# 2040.net
KiCad netlist of a schematic drawn in Altium Designer
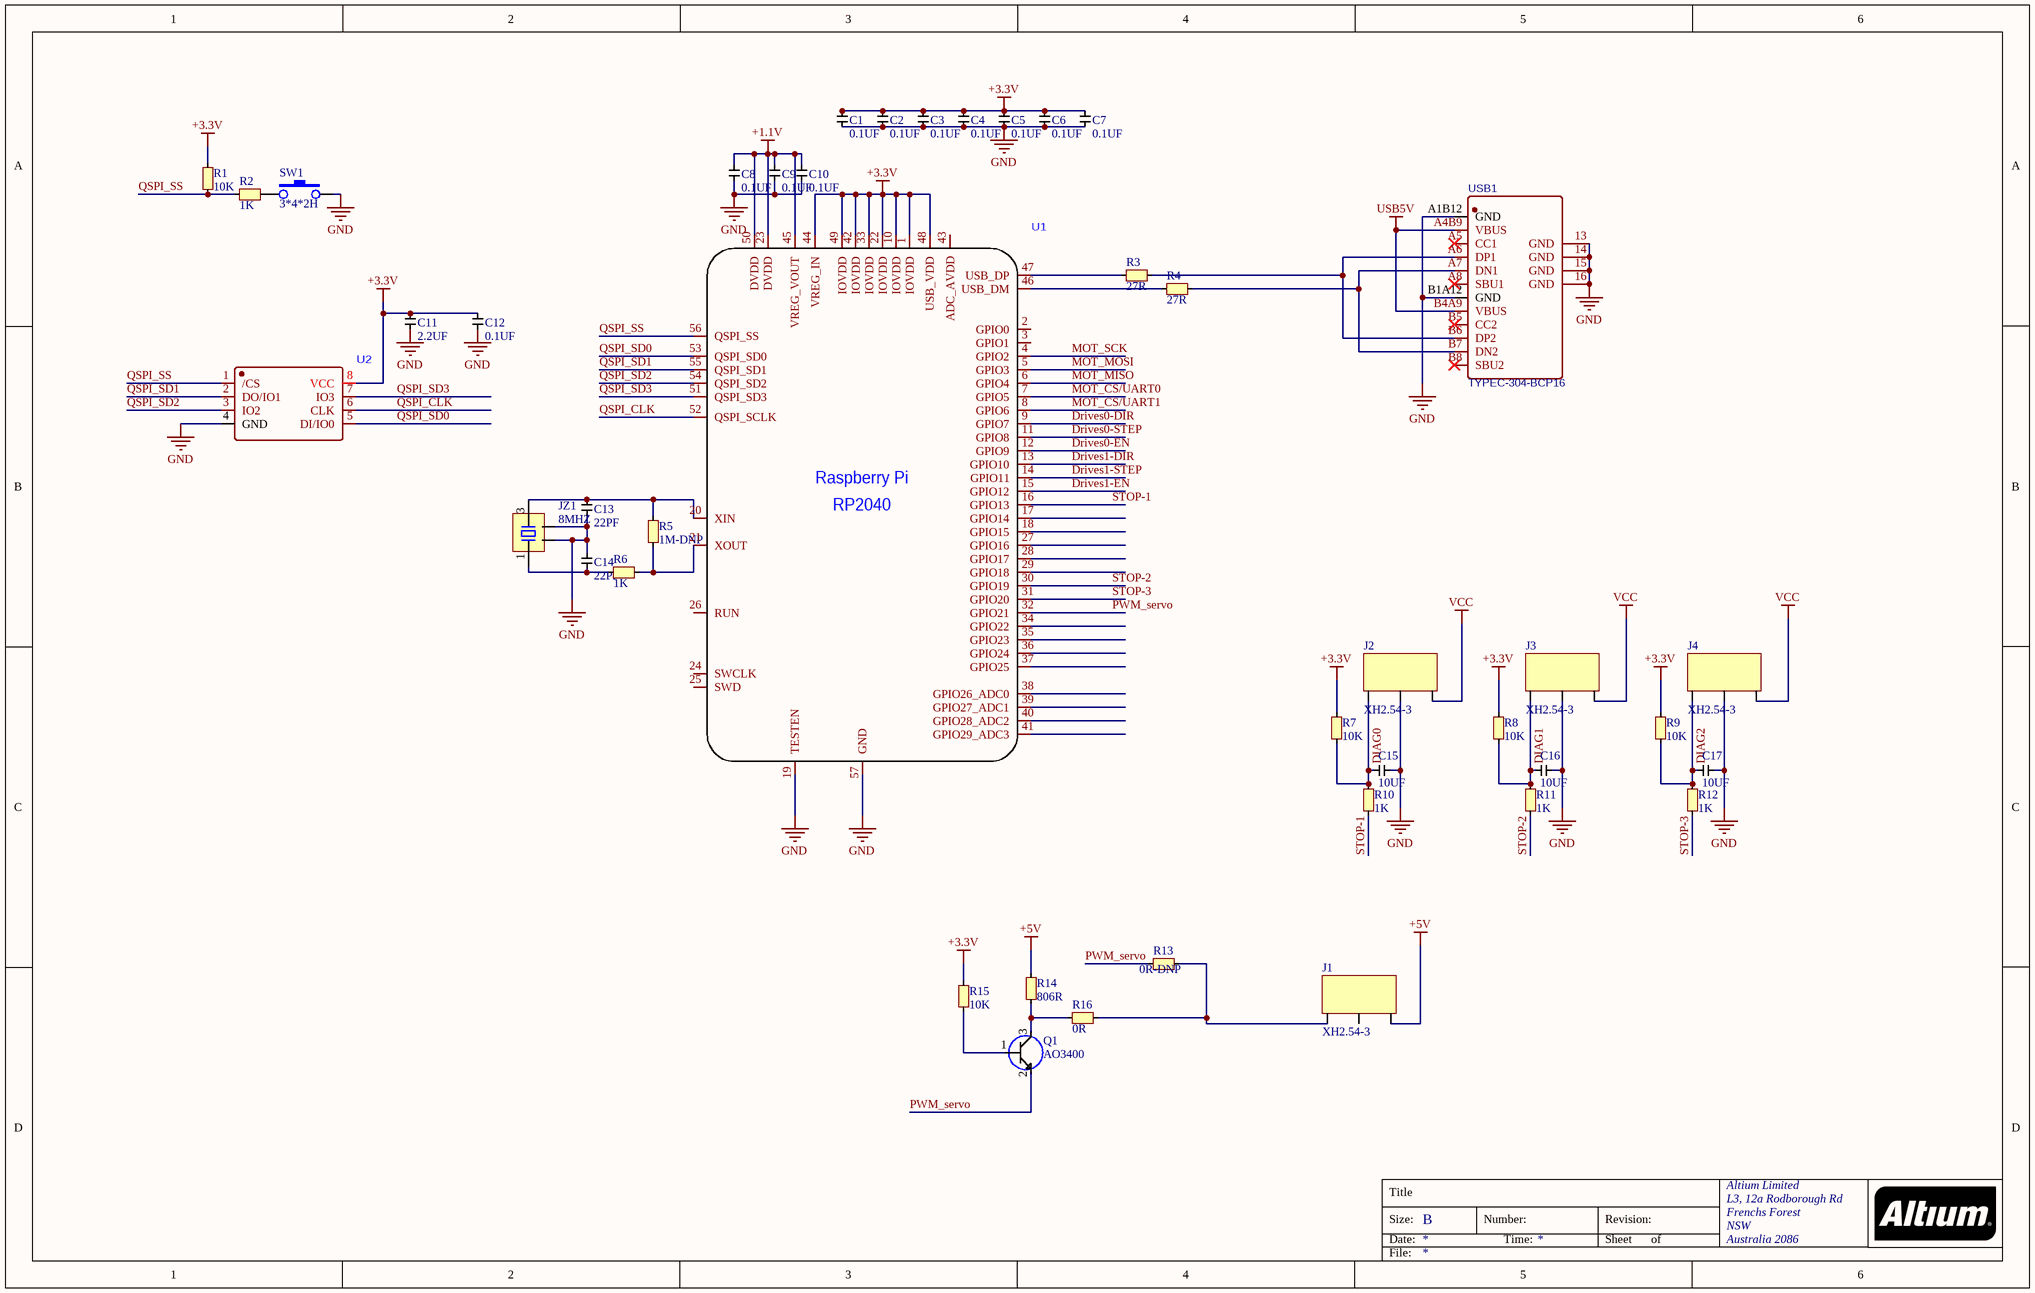
[diagram p0: 2040.SchDoc]

(export (version "E")
  (design (tool "Eeschema 10.0.6"))
  (components
    (comp (ref "C1") (value "0.1UF") (footprint "C0402") (libsource (lib "jx") (part "C")))
    (comp (ref "C2") (value "0.1UF") (footprint "C0402") (libsource (lib "jx") (part "C")))
    (comp (ref "C3") (value "0.1UF") (footprint "C0402") (libsource (lib "jx") (part "C")))
    (comp (ref "C4") (value "0.1UF") (footprint "C0402") (libsource (lib "jx") (part "C")))
    (comp (ref "C5") (value "0.1UF") (footprint "C0402") (libsource (lib "jx") (part "C")))
    (comp (ref "C6") (value "0.1UF") (footprint "C0402") (libsource (lib "jx") (part "C")))
    (comp (ref "C7") (value "0.1UF") (footprint "C0402") (libsource (lib "jx") (part "C")))
    (comp (ref "C8") (value "0.1UF") (footprint "C0402") (libsource (lib "jx") (part "C")))
    (comp (ref "C9") (value "0.1UF") (footprint "C0402") (libsource (lib "jx") (part "C")))
    (comp (ref "C10") (value "0.1UF") (footprint "C0402") (libsource (lib "jx") (part "C")))
    (comp (ref "C11") (value "2.2UF") (footprint "C0402") (libsource (lib "jx") (part "C")))
    (comp (ref "C12") (value "0.1UF") (footprint "C0402") (libsource (lib "jx") (part "C")))
    (comp (ref "C13") (value "22PF") (footprint "0603C") (libsource (lib "jx") (part "0603C")))
    (comp (ref "C14") (value "22PF") (footprint "0603C") (libsource (lib "jx") (part "0603C")))
    (comp (ref "C15") (value "10UF") (footprint "0603C") (libsource (lib "jx") (part "0603C")))
    (comp (ref "C16") (value "10UF") (footprint "0603C") (libsource (lib "jx") (part "0603C")))
    (comp (ref "C17") (value "10UF") (footprint "0603C") (libsource (lib "jx") (part "0603C")))
    (comp (ref "J1")
      (value "XH2.54-3")
      (footprint "JST_XH_B3B-XH-A_1X03_P2.50MM_VERTICAL")
      (libsource (lib "jx") (part "XH2.54-3"))
    )
    (comp (ref "J2")
      (value "XH2.54-3")
      (footprint "JST_XH_B3B-XH-A_1X03_P2.50MM_VERTICAL")
      (libsource (lib "jx") (part "XH2.54-3"))
    )
    (comp (ref "J3")
      (value "XH2.54-3")
      (footprint "JST_XH_B3B-XH-A_1X03_P2.50MM_VERTICAL")
      (libsource (lib "jx") (part "XH2.54-3"))
    )
    (comp (ref "J4")
      (value "XH2.54-3")
      (footprint "JST_XH_B3B-XH-A_1X03_P2.50MM_VERTICAL")
      (libsource (lib "jx") (part "XH2.54-3"))
    )
    (comp (ref "JZ1") (value "8MHZ") (footprint "OSC-3225-4P") (libsource (lib "jx") (part "JZ3225")))
    (comp (ref "Q1") (value "AO3400") (footprint "SOT-23") (libsource (lib "jx") (part "S8050")))
    (comp (ref "R1") (value "10K") (footprint "0603") (libsource (lib "") (part "0603R_3")))
    (comp (ref "R2") (value "1K") (footprint "0603") (libsource (lib "jx") (part "0603R")))
    (comp (ref "R3") (value "27R") (footprint "R0402") (libsource (lib "") (part "R_1")))
    (comp (ref "R4") (value "27R") (footprint "R0402") (libsource (lib "") (part "R_1")))
    (comp (ref "R5") (value "1M-DNP") (footprint "0603") (libsource (lib "") (part "0603R_1")))
    (comp (ref "R6") (value "1K") (footprint "0603") (libsource (lib "") (part "0603R_2")))
    (comp (ref "R7") (value "10K") (footprint "0603") (libsource (lib "") (part "0603R_1")))
    (comp (ref "R8") (value "10K") (footprint "0603") (libsource (lib "") (part "0603R_1")))
    (comp (ref "R9") (value "10K") (footprint "0603") (libsource (lib "") (part "0603R_1")))
    (comp (ref "R10") (value "1K") (footprint "0603") (libsource (lib "") (part "0603R_1")))
    (comp (ref "R11") (value "1K") (footprint "0603") (libsource (lib "") (part "0603R_1")))
    (comp (ref "R12") (value "1K") (footprint "0603") (libsource (lib "") (part "0603R_1")))
    (comp (ref "R13") (value "0R-DNP") (footprint "0603") (libsource (lib "") (part "R_2")))
    (comp (ref "R14") (value "806R") (footprint "0603") (libsource (lib "") (part "R_3")))
    (comp (ref "R15") (value "10K") (footprint "0603") (libsource (lib "jx") (part "R")))
    (comp (ref "R16") (value "0R") (footprint "0603") (libsource (lib "") (part "R_2")))
    (comp (ref "SW1") (value "3*4*2H") (footprint "K") (libsource (lib "jx") (part "RESET")))
    (comp (ref "U1")
      (value "~")
      (footprint "RP2040")
      (libsource (lib "altium-import") (part "root_0_RP2040_"))
    )
    (comp (ref "U2")
      (value "~")
      (footprint "SOP-8")
      (libsource (lib "altium-import") (part "root_0_W25Q16JVSSIQ_"))
    )
    (comp (ref "USB1")
      (value "TYPEC-304-BCP16")
      (footprint "USB-C-SMD_TYPEC-304-BCP16")
      (fields (field (name "BOM_SUPPLIER PART") "C720629") (field (name "CONTRIBUTOR") "LCSC"))
      (libsource (lib "altium-import") (part "root_0_TYPEC-304-BCP16_"))
    )
  )
  (nets
    (net (code "1") (name "+1.1V") (class "Default")
      (node (ref "C10") (pin "1") (pinfunction "1_1") (pintype "passive"))
      (node (ref "C8") (pin "1") (pinfunction "1_1") (pintype "passive"))
      (node (ref "C9") (pin "1") (pinfunction "1_1") (pintype "passive"))
      (node (ref "U1") (pin "23") (pinfunction "DVDD_23") (pintype "passive"))
      (node (ref "U1") (pin "45") (pinfunction "VREG_VOUT_45") (pintype "passive"))
      (node (ref "U1") (pin "50") (pinfunction "DVDD_50") (pintype "passive"))
    )
    (net (code "2") (name "+3.3V") (class "Default")
      (node (ref "C1") (pin "1") (pinfunction "1_1") (pintype "passive"))
      (node (ref "C11") (pin "1") (pinfunction "1_1") (pintype "passive"))
      (node (ref "C12") (pin "1") (pinfunction "1_1") (pintype "passive"))
      (node (ref "C2") (pin "1") (pinfunction "1_1") (pintype "passive"))
      (node (ref "C3") (pin "1") (pinfunction "1_1") (pintype "passive"))
      (node (ref "C4") (pin "1") (pinfunction "1_1") (pintype "passive"))
      (node (ref "C5") (pin "1") (pinfunction "1_1") (pintype "passive"))
      (node (ref "C6") (pin "1") (pinfunction "1_1") (pintype "passive"))
      (node (ref "C7") (pin "1") (pinfunction "1_1") (pintype "passive"))
      (node (ref "R1") (pin "1") (pinfunction "1_1") (pintype "passive"))
      (node (ref "R15") (pin "1") (pinfunction "1_1") (pintype "passive"))
      (node (ref "R7") (pin "2") (pinfunction "2_2") (pintype "passive"))
      (node (ref "R8") (pin "2") (pinfunction "2_2") (pintype "passive"))
      (node (ref "R9") (pin "2") (pinfunction "2_2") (pintype "passive"))
      (node (ref "U1") (pin "1") (pinfunction "IOVDD_1") (pintype "passive"))
      (node (ref "U1") (pin "10") (pinfunction "IOVDD_10") (pintype "passive"))
      (node (ref "U1") (pin "22") (pinfunction "IOVDD_22") (pintype "passive"))
      (node (ref "U1") (pin "33") (pinfunction "IOVDD_33") (pintype "passive"))
      (node (ref "U1") (pin "42") (pinfunction "IOVDD_42") (pintype "passive"))
      (node (ref "U1") (pin "44") (pinfunction "VREG_IN_44") (pintype "passive"))
      (node (ref "U1") (pin "48") (pinfunction "USB_VDD_48") (pintype "passive"))
      (node (ref "U1") (pin "49") (pinfunction "IOVDD_49") (pintype "passive"))
      (node (ref "U2") (pin "8") (pinfunction "VCC_8") (pintype "passive"))
    )
    (net (code "3") (name "+5V") (class "Default")
      (node (ref "J1") (pin "3") (pinfunction "3_3") (pintype "passive"))
      (node (ref "R14") (pin "2") (pinfunction "2_2") (pintype "passive"))
    )
    (net (code "4") (name "/DIAG0") (class "Default")
      (node (ref "C15") (pin "2") (pinfunction "2_2") (pintype "passive"))
      (node (ref "J2") (pin "1") (pinfunction "1_1") (pintype "passive"))
      (node (ref "R10") (pin "2") (pinfunction "2_2") (pintype "passive"))
      (node (ref "R7") (pin "1") (pinfunction "1_1") (pintype "passive"))
    )
    (net (code "5") (name "/DIAG1") (class "Default")
      (node (ref "C16") (pin "2") (pinfunction "2_2") (pintype "passive"))
      (node (ref "J3") (pin "1") (pinfunction "1_1") (pintype "passive"))
      (node (ref "R11") (pin "2") (pinfunction "2_2") (pintype "passive"))
      (node (ref "R8") (pin "1") (pinfunction "1_1") (pintype "passive"))
    )
    (net (code "6") (name "/DIAG2") (class "Default")
      (node (ref "C17") (pin "2") (pinfunction "2_2") (pintype "passive"))
      (node (ref "J4") (pin "1") (pinfunction "1_1") (pintype "passive"))
      (node (ref "R12") (pin "2") (pinfunction "2_2") (pintype "passive"))
      (node (ref "R9") (pin "1") (pinfunction "1_1") (pintype "passive"))
    )
    (net (code "7") (name "/Drives0-DIR") (class "Default")
      (node (ref "U1") (pin "9") (pinfunction "GPIO7_9") (pintype "passive"))
    )
    (net (code "8") (name "/Drives0-EN") (class "Default")
      (node (ref "U1") (pin "12") (pinfunction "GPIO9_12") (pintype "passive"))
    )
    (net (code "9") (name "/Drives0-STEP") (class "Default")
      (node (ref "U1") (pin "11") (pinfunction "GPIO8_11") (pintype "passive"))
    )
    (net (code "10") (name "/Drives1-DIR") (class "Default")
      (node (ref "U1") (pin "13") (pinfunction "GPIO10_13") (pintype "passive"))
    )
    (net (code "11") (name "/Drives1-EN") (class "Default")
      (node (ref "U1") (pin "15") (pinfunction "GPIO12_15") (pintype "passive"))
    )
    (net (code "12") (name "/Drives1-STEP") (class "Default")
      (node (ref "U1") (pin "14") (pinfunction "GPIO11_14") (pintype "passive"))
    )
    (net (code "13") (name "/MOT_CS{slash}UART0") (class "Default")
      (node (ref "U1") (pin "7") (pinfunction "GPIO5_7") (pintype "passive"))
    )
    (net (code "14") (name "/MOT_CS{slash}UART1") (class "Default")
      (node (ref "U1") (pin "8") (pinfunction "GPIO6_8") (pintype "passive"))
    )
    (net (code "15") (name "/MOT_MISO") (class "Default")
      (node (ref "U1") (pin "6") (pinfunction "GPIO4_6") (pintype "passive"))
    )
    (net (code "16") (name "/MOT_MOSI") (class "Default")
      (node (ref "U1") (pin "5") (pinfunction "GPIO3_5") (pintype "passive"))
    )
    (net (code "17") (name "/MOT_SCK") (class "Default")
      (node (ref "U1") (pin "4") (pinfunction "GPIO2_4") (pintype "passive"))
    )
    (net (code "18") (name "/PWM_servo") (class "Default")
      (node (ref "Q1") (pin "2") (pinfunction "2_2") (pintype "passive"))
      (node (ref "R13") (pin "2") (pinfunction "2_2") (pintype "passive"))
      (node (ref "U1") (pin "32") (pinfunction "GPIO21_32") (pintype "passive"))
    )
    (net (code "19") (name "/QSPI_CLK") (class "Default")
      (node (ref "U1") (pin "52") (pinfunction "QSPI_SCLK_52") (pintype "passive"))
      (node (ref "U2") (pin "6") (pinfunction "CLK_6") (pintype "passive"))
    )
    (net (code "20") (name "/QSPI_SD0") (class "Default")
      (node (ref "U1") (pin "53") (pinfunction "QSPI_SD0_53") (pintype "passive"))
      (node (ref "U2") (pin "5") (pinfunction "DI/IO0_5") (pintype "passive"))
    )
    (net (code "21") (name "/QSPI_SD1") (class "Default")
      (node (ref "U1") (pin "55") (pinfunction "QSPI_SD1_55") (pintype "passive"))
      (node (ref "U2") (pin "2") (pinfunction "DO/IO1_2") (pintype "passive"))
    )
    (net (code "22") (name "/QSPI_SD2") (class "Default")
      (node (ref "U1") (pin "54") (pinfunction "QSPI_SD2_54") (pintype "passive"))
      (node (ref "U2") (pin "3") (pinfunction "IO2_3") (pintype "passive"))
    )
    (net (code "23") (name "/QSPI_SD3") (class "Default")
      (node (ref "U1") (pin "51") (pinfunction "QSPI_SD3_51") (pintype "passive"))
      (node (ref "U2") (pin "7") (pinfunction "IO3_7") (pintype "passive"))
    )
    (net (code "24") (name "/QSPI_SS") (class "Default")
      (node (ref "R1") (pin "2") (pinfunction "2_2") (pintype "passive"))
      (node (ref "R2") (pin "1") (pinfunction "1_1") (pintype "passive"))
      (node (ref "U1") (pin "56") (pinfunction "QSPI_SS_56") (pintype "passive"))
      (node (ref "U2") (pin "1") (pinfunction "/CS_1") (pintype "passive"))
    )
    (net (code "25") (name "/STOP-1") (class "Default")
      (node (ref "R10") (pin "1") (pinfunction "1_1") (pintype "passive"))
      (node (ref "U1") (pin "16") (pinfunction "GPIO13_16") (pintype "passive"))
    )
    (net (code "26") (name "/STOP-2") (class "Default")
      (node (ref "R11") (pin "1") (pinfunction "1_1") (pintype "passive"))
      (node (ref "U1") (pin "30") (pinfunction "GPIO19_30") (pintype "passive"))
    )
    (net (code "27") (name "/STOP-3") (class "Default")
      (node (ref "R12") (pin "1") (pinfunction "1_1") (pintype "passive"))
      (node (ref "U1") (pin "31") (pinfunction "GPIO20_31") (pintype "passive"))
    )
    (net (code "28") (name "GND") (class "Default")
      (node (ref "C1") (pin "2") (pinfunction "2_2") (pintype "passive"))
      (node (ref "C10") (pin "2") (pinfunction "2_2") (pintype "passive"))
      (node (ref "C11") (pin "2") (pinfunction "2_2") (pintype "passive"))
      (node (ref "C12") (pin "2") (pinfunction "2_2") (pintype "passive"))
      (node (ref "C13") (pin "2") (pinfunction "2_2") (pintype "passive"))
      (node (ref "C14") (pin "1") (pinfunction "1_1") (pintype "passive"))
      (node (ref "C15") (pin "1") (pinfunction "1_1") (pintype "passive"))
      (node (ref "C16") (pin "1") (pinfunction "1_1") (pintype "passive"))
      (node (ref "C17") (pin "1") (pinfunction "1_1") (pintype "passive"))
      (node (ref "C2") (pin "2") (pinfunction "2_2") (pintype "passive"))
      (node (ref "C3") (pin "2") (pinfunction "2_2") (pintype "passive"))
      (node (ref "C4") (pin "2") (pinfunction "2_2") (pintype "passive"))
      (node (ref "C5") (pin "2") (pinfunction "2_2") (pintype "passive"))
      (node (ref "C6") (pin "2") (pinfunction "2_2") (pintype "passive"))
      (node (ref "C7") (pin "2") (pinfunction "2_2") (pintype "passive"))
      (node (ref "C8") (pin "2") (pinfunction "2_2") (pintype "passive"))
      (node (ref "C9") (pin "2") (pinfunction "2_2") (pintype "passive"))
      (node (ref "J2") (pin "2") (pinfunction "2_2") (pintype "passive"))
      (node (ref "J3") (pin "2") (pinfunction "2_2") (pintype "passive"))
      (node (ref "J4") (pin "2") (pinfunction "2_2") (pintype "passive"))
      (node (ref "JZ1") (pin "2") (pinfunction "2_2") (pintype "passive"))
      (node (ref "JZ1") (pin "4") (pinfunction "4_4") (pintype "passive"))
      (node (ref "SW1") (pin "2") (pinfunction "2_2") (pintype "passive"))
      (node (ref "U1") (pin "19") (pinfunction "TESTEN_19") (pintype "passive"))
      (node (ref "U1") (pin "57") (pinfunction "GND_57") (pintype "passive"))
      (node (ref "U2") (pin "4") (pinfunction "GND_4") (pintype "passive"))
      (node (ref "USB1") (pin "13") (pinfunction "GND_13") (pintype "passive"))
      (node (ref "USB1") (pin "14") (pinfunction "GND_14") (pintype "passive"))
      (node (ref "USB1") (pin "15") (pinfunction "GND_15") (pintype "passive"))
      (node (ref "USB1") (pin "16") (pinfunction "GND_16") (pintype "passive"))
      (node (ref "USB1") (pin "A1B12") (pinfunction "GND_A1B12") (pintype "passive"))
      (node (ref "USB1") (pin "B1A12") (pinfunction "GND_B1A12") (pintype "passive"))
    )
    (net (code "29") (name "Net-(C14-Pad2)") (class "Default")
      (node (ref "C14") (pin "2") (pinfunction "2_2") (pintype "passive"))
      (node (ref "JZ1") (pin "1") (pinfunction "1_1") (pintype "passive"))
      (node (ref "R6") (pin "2") (pinfunction "2_2") (pintype "passive"))
    )
    (net (code "30") (name "Net-(J1-Pad1)") (class "Default")
      (node (ref "J1") (pin "1") (pinfunction "1_1") (pintype "passive"))
      (node (ref "R13") (pin "1") (pinfunction "1_1") (pintype "passive"))
      (node (ref "R16") (pin "1") (pinfunction "1_1") (pintype "passive"))
    )
    (net (code "31") (name "Net-(Q1-Pad1)") (class "Default")
      (node (ref "Q1") (pin "1") (pinfunction "1_1") (pintype "passive"))
      (node (ref "R15") (pin "2") (pinfunction "2_2") (pintype "passive"))
    )
    (net (code "32") (name "Net-(Q1-Pad3)") (class "Default")
      (node (ref "Q1") (pin "3") (pinfunction "3_3") (pintype "passive"))
      (node (ref "R14") (pin "1") (pinfunction "1_1") (pintype "passive"))
      (node (ref "R16") (pin "2") (pinfunction "2_2") (pintype "passive"))
    )
    (net (code "33") (name "Net-(R2-Pad2)") (class "Default")
      (node (ref "R2") (pin "2") (pinfunction "2_2") (pintype "passive"))
      (node (ref "SW1") (pin "1") (pinfunction "1_1") (pintype "passive"))
    )
    (net (code "34") (name "Net-(U1-USB_DM)") (class "Default")
      (node (ref "R4") (pin "1") (pinfunction "1_1") (pintype "passive"))
      (node (ref "U1") (pin "46") (pinfunction "USB_DM_46") (pintype "passive"))
    )
    (net (code "35") (name "Net-(U1-USB_DP)") (class "Default")
      (node (ref "R3") (pin "1") (pinfunction "1_1") (pintype "passive"))
      (node (ref "U1") (pin "47") (pinfunction "USB_DP_47") (pintype "passive"))
    )
    (net (code "36") (name "Net-(U1-XIN)") (class "Default")
      (node (ref "C13") (pin "1") (pinfunction "1_1") (pintype "passive"))
      (node (ref "JZ1") (pin "3") (pinfunction "3_3") (pintype "passive"))
      (node (ref "R5") (pin "2") (pinfunction "2_2") (pintype "passive"))
      (node (ref "U1") (pin "20") (pinfunction "XIN_20") (pintype "passive"))
    )
    (net (code "37") (name "Net-(U1-XOUT)") (class "Default")
      (node (ref "R5") (pin "1") (pinfunction "1_1") (pintype "passive"))
      (node (ref "R6") (pin "1") (pinfunction "1_1") (pintype "passive"))
      (node (ref "U1") (pin "21") (pinfunction "XOUT_21") (pintype "passive"))
    )
    (net (code "38") (name "Net-(USB1-DN1)") (class "Default")
      (node (ref "R4") (pin "2") (pinfunction "2_2") (pintype "passive"))
      (node (ref "USB1") (pin "A7") (pinfunction "DN1_A7") (pintype "passive"))
      (node (ref "USB1") (pin "B7") (pinfunction "DN2_B7") (pintype "passive"))
    )
    (net (code "39") (name "Net-(USB1-DP1)") (class "Default")
      (node (ref "R3") (pin "2") (pinfunction "2_2") (pintype "passive"))
      (node (ref "USB1") (pin "A6") (pinfunction "DP1_A6") (pintype "passive"))
      (node (ref "USB1") (pin "B6") (pinfunction "DP2_B6") (pintype "passive"))
    )
    (net (code "40") (name "USB5V") (class "Default")
      (node (ref "USB1") (pin "A4B9") (pinfunction "VBUS_A4B9") (pintype "passive"))
      (node (ref "USB1") (pin "B4A9") (pinfunction "VBUS_B4A9") (pintype "passive"))
    )
    (net (code "41") (name "VCC") (class "Default")
      (node (ref "J2") (pin "3") (pinfunction "3_3") (pintype "passive"))
      (node (ref "J3") (pin "3") (pinfunction "3_3") (pintype "passive"))
      (node (ref "J4") (pin "3") (pinfunction "3_3") (pintype "passive"))
    )
    (net (code "42") (name "unconnected-(J1-Pad2)") (class "Default")
      (node (ref "J1") (pin "2") (pinfunction "2_2") (pintype "passive"))
    )
    (net (code "43") (name "unconnected-(U1-ADC_AVDD-Pad43)") (class "Default")
      (node (ref "U1") (pin "43") (pinfunction "ADC_AVDD_43") (pintype "passive"))
    )
    (net (code "44") (name "unconnected-(U1-GPIO0-Pad2)") (class "Default")
      (node (ref "U1") (pin "2") (pinfunction "GPIO0_2") (pintype "passive"))
    )
    (net (code "45") (name "unconnected-(U1-GPIO1-Pad3)") (class "Default")
      (node (ref "U1") (pin "3") (pinfunction "GPIO1_3") (pintype "passive"))
    )
    (net (code "46") (name "unconnected-(U1-GPIO14-Pad17)") (class "Default")
      (node (ref "U1") (pin "17") (pinfunction "GPIO14_17") (pintype "passive"))
    )
    (net (code "47") (name "unconnected-(U1-GPIO15-Pad18)") (class "Default")
      (node (ref "U1") (pin "18") (pinfunction "GPIO15_18") (pintype "passive"))
    )
    (net (code "48") (name "unconnected-(U1-GPIO16-Pad27)") (class "Default")
      (node (ref "U1") (pin "27") (pinfunction "GPIO16_27") (pintype "passive"))
    )
    (net (code "49") (name "unconnected-(U1-GPIO17-Pad28)") (class "Default")
      (node (ref "U1") (pin "28") (pinfunction "GPIO17_28") (pintype "passive"))
    )
    (net (code "50") (name "unconnected-(U1-GPIO18-Pad29)") (class "Default")
      (node (ref "U1") (pin "29") (pinfunction "GPIO18_29") (pintype "passive"))
    )
    (net (code "51") (name "unconnected-(U1-GPIO22-Pad34)") (class "Default")
      (node (ref "U1") (pin "34") (pinfunction "GPIO22_34") (pintype "passive"))
    )
    (net (code "52") (name "unconnected-(U1-GPIO23-Pad35)") (class "Default")
      (node (ref "U1") (pin "35") (pinfunction "GPIO23_35") (pintype "passive"))
    )
    (net (code "53") (name "unconnected-(U1-GPIO24-Pad36)") (class "Default")
      (node (ref "U1") (pin "36") (pinfunction "GPIO24_36") (pintype "passive"))
    )
    (net (code "54") (name "unconnected-(U1-GPIO25-Pad37)") (class "Default")
      (node (ref "U1") (pin "37") (pinfunction "GPIO25_37") (pintype "passive"))
    )
    (net (code "55") (name "unconnected-(U1-GPIO26_ADC0-Pad38)") (class "Default")
      (node (ref "U1") (pin "38") (pinfunction "GPIO26_ADC0_38") (pintype "passive"))
    )
    (net (code "56") (name "unconnected-(U1-GPIO27_ADC1-Pad39)") (class "Default")
      (node (ref "U1") (pin "39") (pinfunction "GPIO27_ADC1_39") (pintype "passive"))
    )
    (net (code "57") (name "unconnected-(U1-GPIO28_ADC2-Pad40)") (class "Default")
      (node (ref "U1") (pin "40") (pinfunction "GPIO28_ADC2_40") (pintype "passive"))
    )
    (net (code "58") (name "unconnected-(U1-GPIO29_ADC3-Pad41)") (class "Default")
      (node (ref "U1") (pin "41") (pinfunction "GPIO29_ADC3_41") (pintype "passive"))
    )
    (net (code "59") (name "unconnected-(U1-RUN-Pad26)") (class "Default")
      (node (ref "U1") (pin "26") (pinfunction "RUN_26") (pintype "passive"))
    )
    (net (code "60") (name "unconnected-(U1-SWCLK-Pad24)") (class "Default")
      (node (ref "U1") (pin "24") (pinfunction "SWCLK_24") (pintype "passive"))
    )
    (net (code "61") (name "unconnected-(U1-SWD-Pad25)") (class "Default")
      (node (ref "U1") (pin "25") (pinfunction "SWD_25") (pintype "passive"))
    )
    (net (code "62") (name "unconnected-(USB1-CC1-PadA5)") (class "Default")
      (node (ref "USB1") (pin "A5") (pinfunction "CC1_A5") (pintype "passive+no_connect"))
    )
    (net (code "63") (name "unconnected-(USB1-CC2-PadB5)") (class "Default")
      (node (ref "USB1") (pin "B5") (pinfunction "CC2_B5") (pintype "passive+no_connect"))
    )
    (net (code "64") (name "unconnected-(USB1-SBU1-PadA8)") (class "Default")
      (node (ref "USB1") (pin "A8") (pinfunction "SBU1_A8") (pintype "passive+no_connect"))
    )
    (net (code "65") (name "unconnected-(USB1-SBU2-PadB8)") (class "Default")
      (node (ref "USB1") (pin "B8") (pinfunction "SBU2_B8") (pintype "passive+no_connect"))
    )
  )
)
